# axiom_beta_interface_dummy_v0_13_r1_2_e8.net
KiCad netlist of a schematic drawn in EAGLE
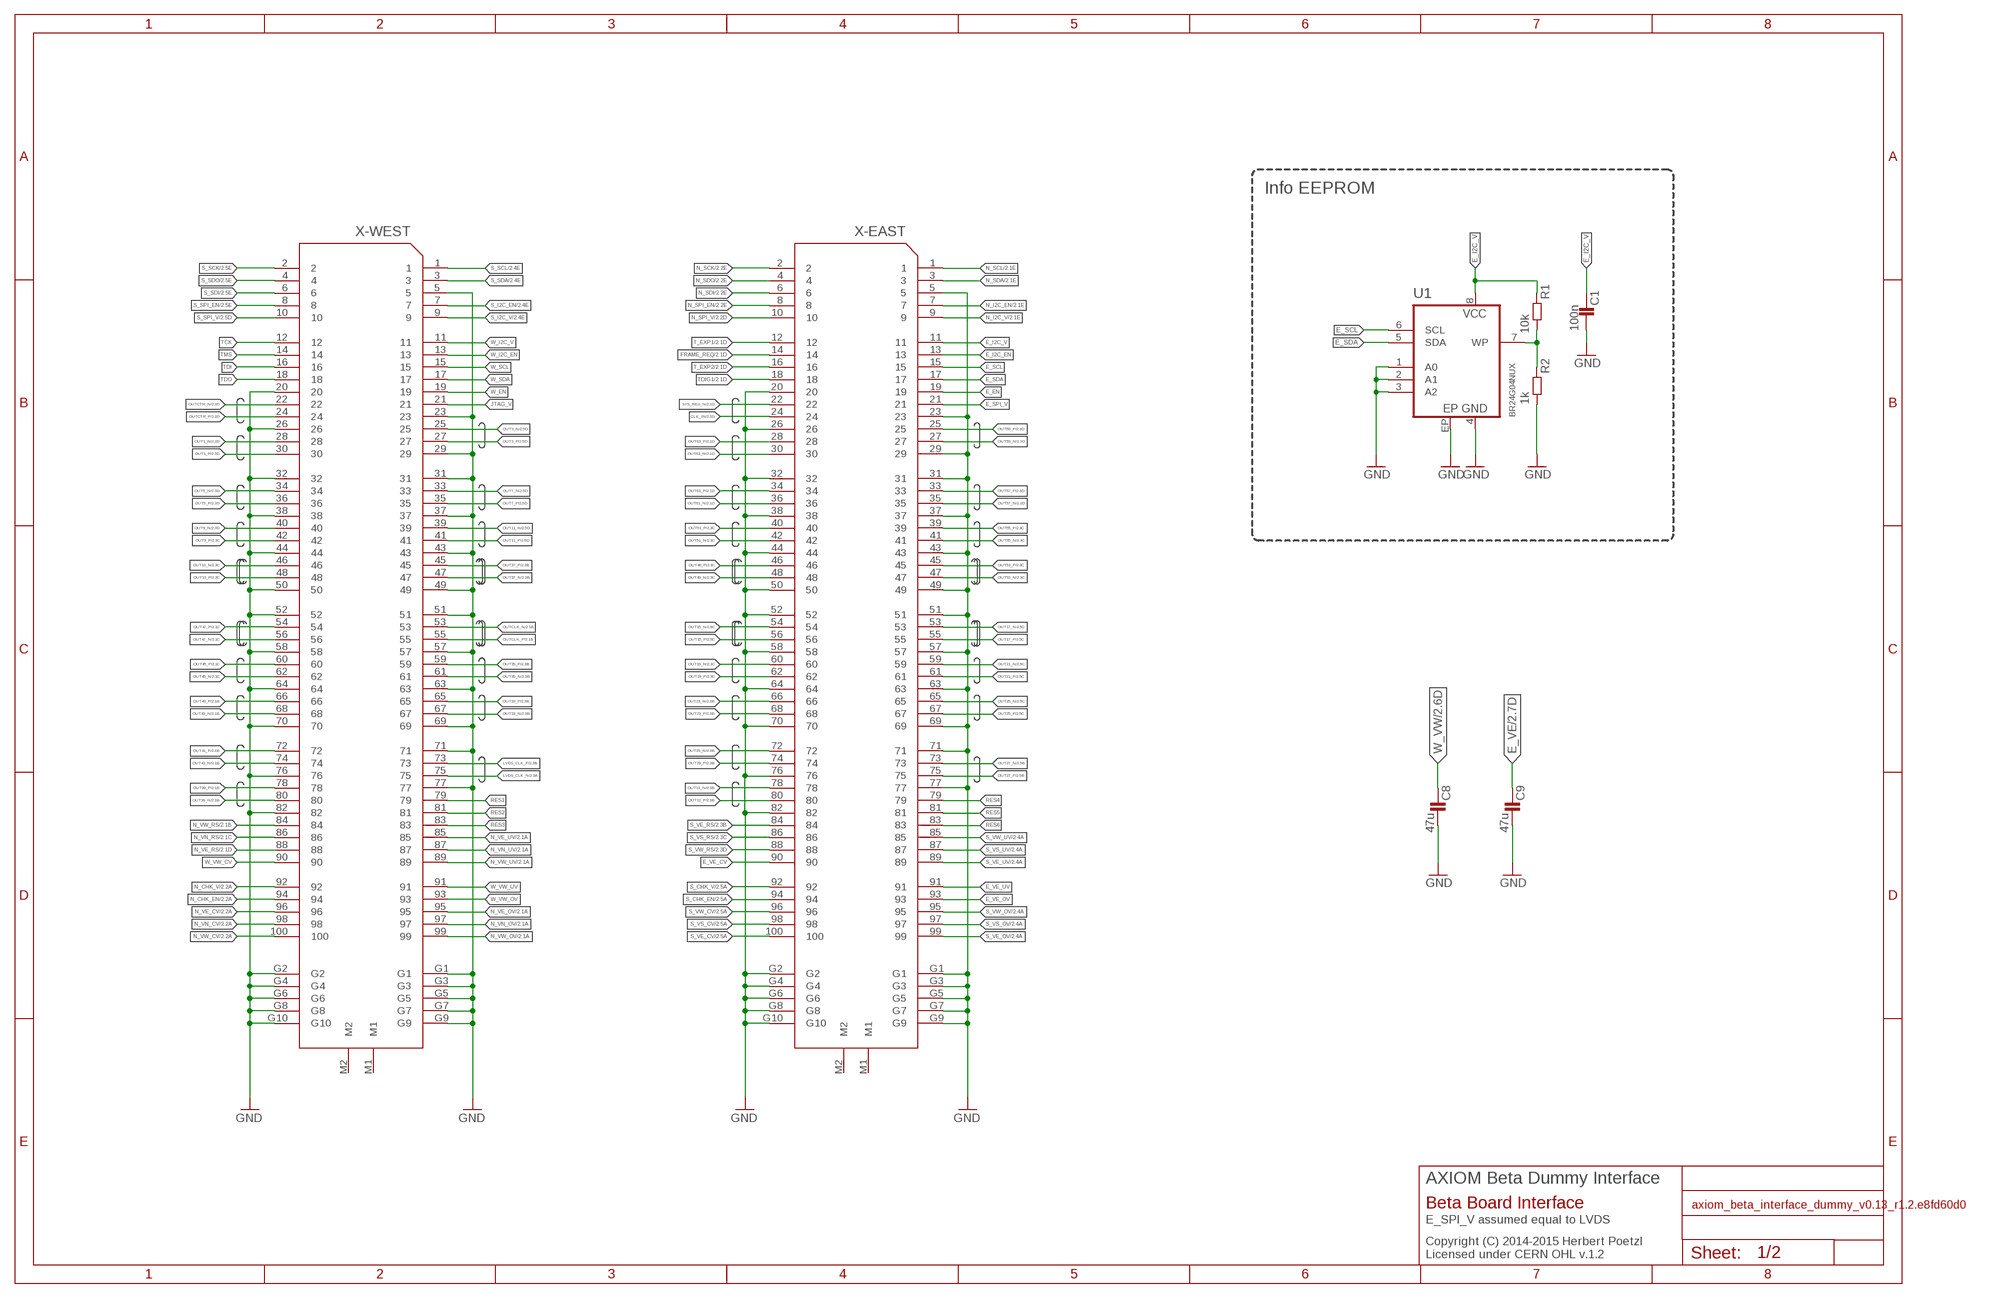
[diagram p0: schematic, sheet 1]
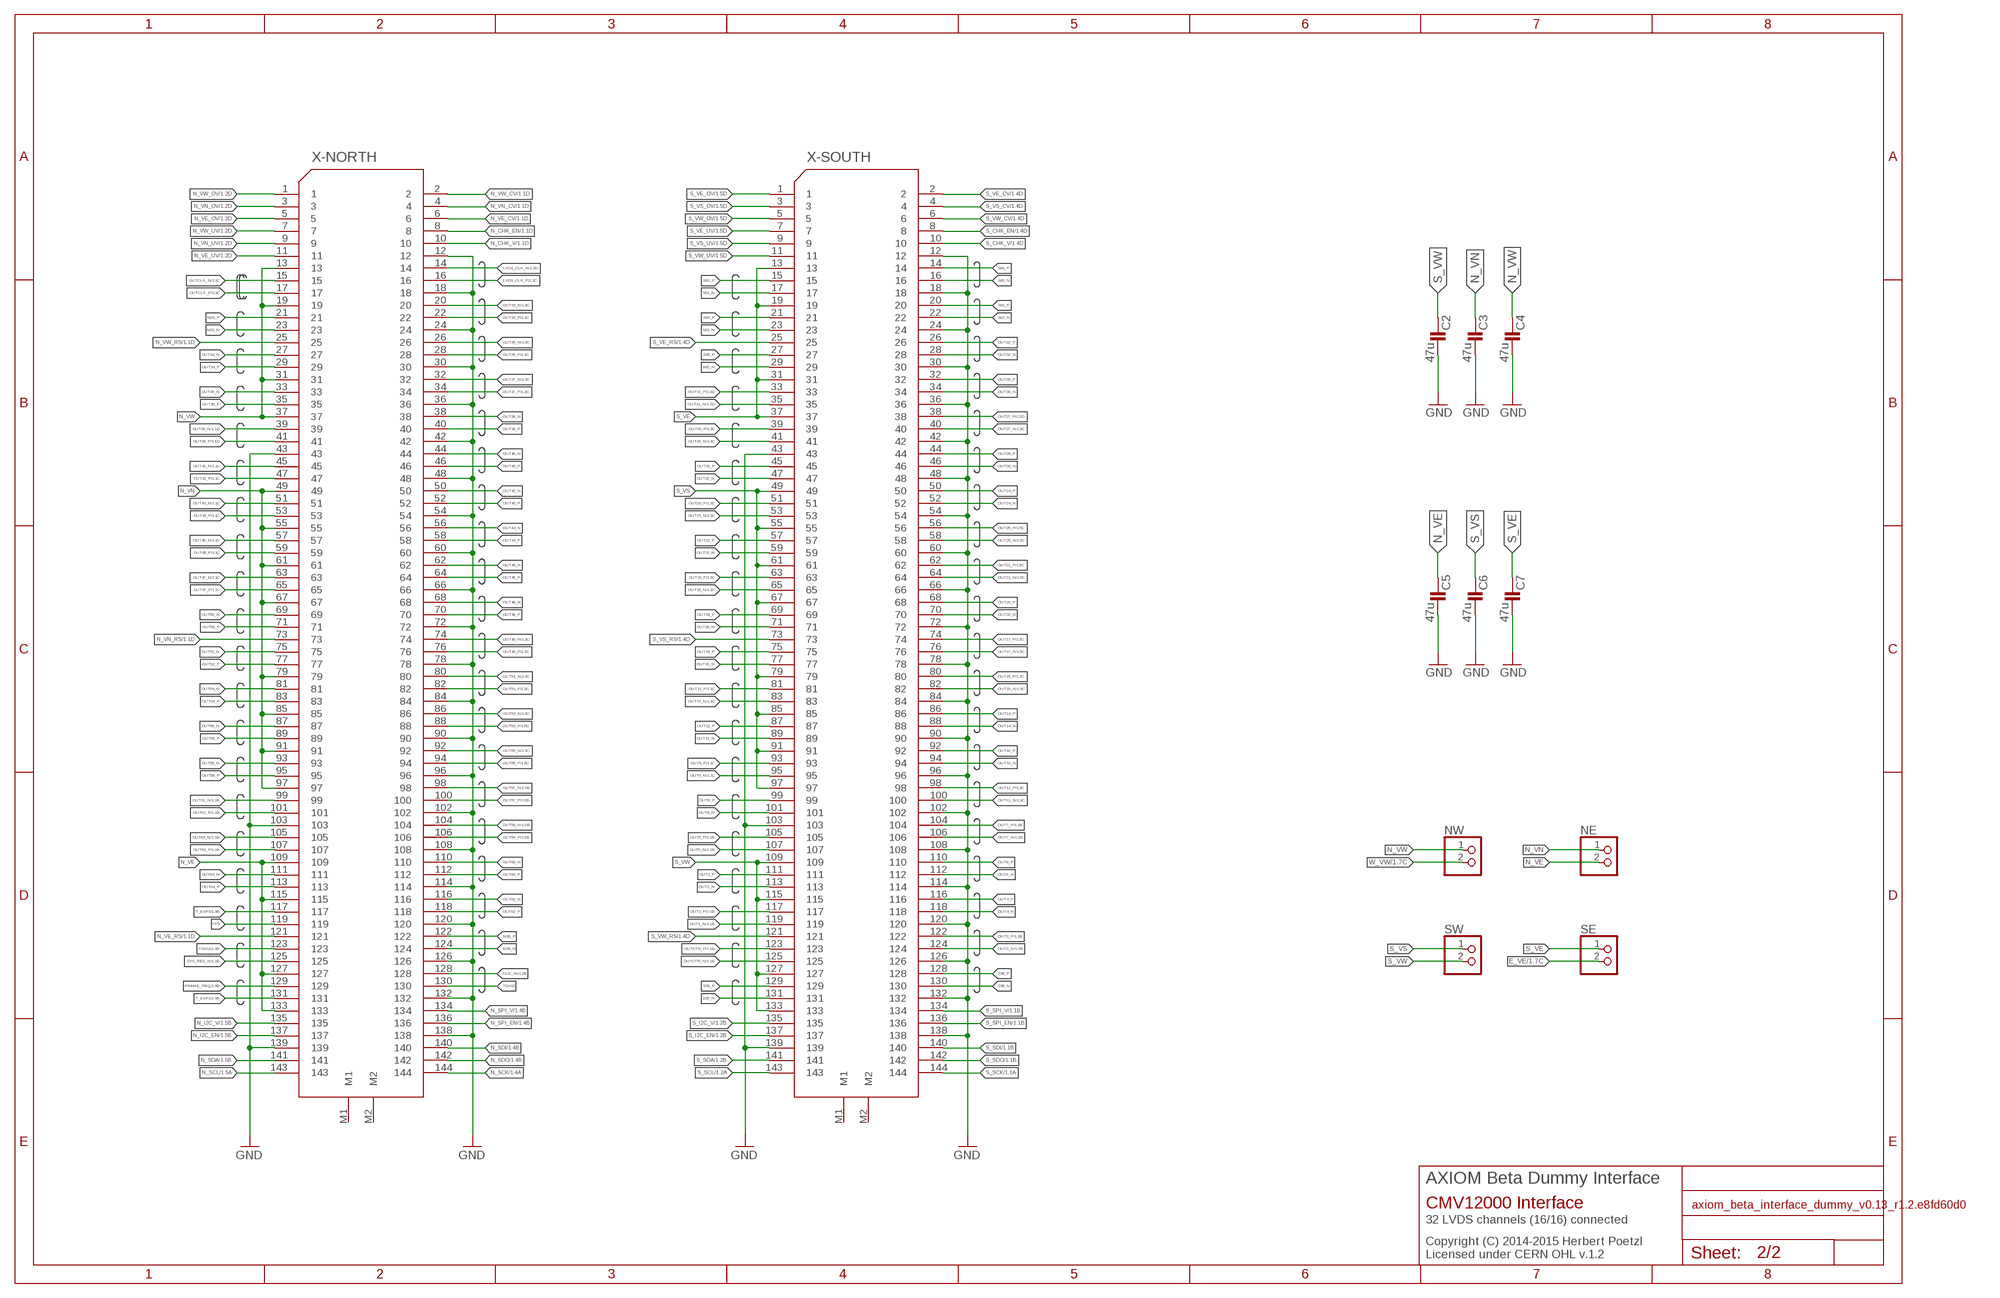
[diagram p1: schematic, sheet 2]

(export (version "E")
  (design (tool "Eeschema 10.0.6"))
  (components
    (comp (ref "C1")
      (value "100n")
      (footprint "eagle-import:0402-B")
      (libsource (lib "eagle-import") (part "C0402-B"))
    )
    (comp (ref "C8")
      (value "47u")
      (footprint "eagle-import:0805-B")
      (libsource (lib "eagle-import") (part "C0805-B"))
    )
    (comp (ref "C9")
      (value "47u")
      (footprint "eagle-import:0805-B")
      (libsource (lib "eagle-import") (part "C0805-B"))
    )
    (comp (ref "R1")
      (value "10k")
      (footprint "eagle-import:0402-B")
      (libsource (lib "eagle-import") (part "R0402-B"))
    )
    (comp (ref "R2")
      (value "1k")
      (footprint "eagle-import:0402-B")
      (libsource (lib "eagle-import") (part "R0402-B"))
    )
    (comp (ref "U1")
      (value "BR24G04NUX")
      (footprint "eagle-import:DFN200X300X100-9N")
      (libsource (lib "eagle-import") (part "BR24G04NUX"))
    )
    (comp (ref "X-EAST")
      (value "FX10-100/10P")
      (footprint "eagle-import:FX10A-100P_10")
      (libsource (lib "eagle-import") (part "FX10-100/10P"))
    )
    (comp (ref "X-WEST")
      (value "FX10-100/10P")
      (footprint "eagle-import:FX10A-100P_10")
      (libsource (lib "eagle-import") (part "FX10-100/10P"))
    )
    (comp (ref "C2")
      (value "47u")
      (footprint "eagle-import:0805-B")
      (libsource (lib "eagle-import") (part "C0805-B"))
    )
    (comp (ref "C3")
      (value "47u")
      (footprint "eagle-import:0805-B")
      (libsource (lib "eagle-import") (part "C0805-B"))
    )
    (comp (ref "C4")
      (value "47u")
      (footprint "eagle-import:0805-B")
      (libsource (lib "eagle-import") (part "C0805-B"))
    )
    (comp (ref "C5")
      (value "47u")
      (footprint "eagle-import:0805-B")
      (libsource (lib "eagle-import") (part "C0805-B"))
    )
    (comp (ref "C6")
      (value "47u")
      (footprint "eagle-import:0805-B")
      (libsource (lib "eagle-import") (part "C0805-B"))
    )
    (comp (ref "C7")
      (value "47u")
      (footprint "eagle-import:0805-B")
      (libsource (lib "eagle-import") (part "C0805-B"))
    )
    (comp (ref "NE")
      (value "PINHD-1X02_2.54")
      (footprint "eagle-import:1X02")
      (libsource (lib "eagle-import") (part "PINHD-1X02_2.54"))
    )
    (comp (ref "NW")
      (value "PINHD-1X02_2.54")
      (footprint "eagle-import:1X02")
      (libsource (lib "eagle-import") (part "PINHD-1X02_2.54"))
    )
    (comp (ref "SE")
      (value "PINHD-1X02_2.54")
      (footprint "eagle-import:1X02")
      (libsource (lib "eagle-import") (part "PINHD-1X02_2.54"))
    )
    (comp (ref "SW")
      (value "PINHD-1X02_2.54")
      (footprint "eagle-import:1X02")
      (libsource (lib "eagle-import") (part "PINHD-1X02_2.54"))
    )
    (comp (ref "X-NORTH")
      (value "FX10-144S")
      (footprint "eagle-import:FX10A-144S")
      (libsource (lib "eagle-import") (part "FX10-144S"))
    )
    (comp (ref "X-SOUTH")
      (value "FX10-144S")
      (footprint "eagle-import:FX10A-144S")
      (libsource (lib "eagle-import") (part "FX10-144S"))
    )
  )
  (nets
    (net (code "1") (name "CLK_IN") (class "Default")
      (node (ref "X-EAST") (pin "24") (pinfunction "24_24") (pintype "bidirectional"))
      (node (ref "X-NORTH") (pin "128") (pinfunction "128_128") (pintype "bidirectional"))
    )
    (net (code "2") (name "E_EN") (class "Default")
      (node (ref "X-EAST") (pin "19") (pinfunction "19_19") (pintype "bidirectional"))
    )
    (net (code "3") (name "E_I2C_EN") (class "Default")
      (node (ref "X-EAST") (pin "13") (pinfunction "13_13") (pintype "bidirectional"))
    )
    (net (code "4") (name "E_I2C_V") (class "Default")
      (node (ref "C1") (pin "1") (pinfunction "1_1") (pintype "passive"))
      (node (ref "R1") (pin "1") (pinfunction "1_1") (pintype "passive"))
      (node (ref "U1") (pin "8") (pinfunction "VCC_8") (pintype "power_in"))
      (node (ref "X-EAST") (pin "11") (pinfunction "11_11") (pintype "bidirectional"))
    )
    (net (code "5") (name "E_SCL") (class "Default")
      (node (ref "U1") (pin "6") (pinfunction "SCL_6") (pintype "input"))
      (node (ref "X-EAST") (pin "15") (pinfunction "15_15") (pintype "bidirectional"))
    )
    (net (code "6") (name "E_SDA") (class "Default")
      (node (ref "U1") (pin "5") (pinfunction "SDA_5") (pintype "bidirectional"))
      (node (ref "X-EAST") (pin "17") (pinfunction "17_17") (pintype "bidirectional"))
    )
    (net (code "7") (name "E_SPI_V") (class "Default")
      (node (ref "X-EAST") (pin "21") (pinfunction "21_21") (pintype "bidirectional"))
    )
    (net (code "8") (name "E_VE") (class "Default")
      (node (ref "C9") (pin "1") (pinfunction "1_1") (pintype "passive"))
      (node (ref "SE") (pin "2") (pinfunction "2_2") (pintype "passive"))
    )
    (net (code "9") (name "E_VE_CV") (class "Default")
      (node (ref "X-EAST") (pin "90") (pinfunction "90_90") (pintype "bidirectional"))
    )
    (net (code "10") (name "E_VE_OV") (class "Default")
      (node (ref "X-EAST") (pin "93") (pinfunction "93_93") (pintype "bidirectional"))
    )
    (net (code "11") (name "E_VE_UV") (class "Default")
      (node (ref "X-EAST") (pin "91") (pinfunction "91_91") (pintype "bidirectional"))
    )
    (net (code "12") (name "FRAME_REQ") (class "Default")
      (node (ref "X-EAST") (pin "14") (pinfunction "14_14") (pintype "bidirectional"))
      (node (ref "X-NORTH") (pin "129") (pinfunction "129_129") (pintype "bidirectional"))
    )
    (net (code "13") (name "GND") (class "Default")
      (node (ref "C1") (pin "2") (pinfunction "2_2") (pintype "passive"))
      (node (ref "C2") (pin "2") (pinfunction "2_2") (pintype "passive"))
      (node (ref "C3") (pin "2") (pinfunction "2_2") (pintype "passive"))
      (node (ref "C4") (pin "2") (pinfunction "2_2") (pintype "passive"))
      (node (ref "C5") (pin "2") (pinfunction "2_2") (pintype "passive"))
      (node (ref "C6") (pin "2") (pinfunction "2_2") (pintype "passive"))
      (node (ref "C7") (pin "2") (pinfunction "2_2") (pintype "passive"))
      (node (ref "C8") (pin "2") (pinfunction "2_2") (pintype "passive"))
      (node (ref "C9") (pin "2") (pinfunction "2_2") (pintype "passive"))
      (node (ref "R2") (pin "2") (pinfunction "2_2") (pintype "passive"))
      (node (ref "U1") (pin "1") (pinfunction "A0_1") (pintype "input"))
      (node (ref "U1") (pin "2") (pinfunction "A1_2") (pintype "input"))
      (node (ref "U1") (pin "3") (pinfunction "A2_3") (pintype "input"))
      (node (ref "U1") (pin "4") (pinfunction "GND_4") (pintype "passive"))
      (node (ref "U1") (pin "EP") (pinfunction "EP_EP") (pintype "passive"))
      (node (ref "X-EAST") (pin "20") (pinfunction "20_20") (pintype "bidirectional"))
      (node (ref "X-EAST") (pin "23") (pinfunction "23_23") (pintype "bidirectional"))
      (node (ref "X-EAST") (pin "26") (pinfunction "26_26") (pintype "bidirectional"))
      (node (ref "X-EAST") (pin "29") (pinfunction "29_29") (pintype "bidirectional"))
      (node (ref "X-EAST") (pin "31") (pinfunction "31_31") (pintype "bidirectional"))
      (node (ref "X-EAST") (pin "32") (pinfunction "32_32") (pintype "bidirectional"))
      (node (ref "X-EAST") (pin "37") (pinfunction "37_37") (pintype "bidirectional"))
      (node (ref "X-EAST") (pin "38") (pinfunction "38_38") (pintype "bidirectional"))
      (node (ref "X-EAST") (pin "43") (pinfunction "43_43") (pintype "bidirectional"))
      (node (ref "X-EAST") (pin "44") (pinfunction "44_44") (pintype "bidirectional"))
      (node (ref "X-EAST") (pin "49") (pinfunction "49_49") (pintype "bidirectional"))
      (node (ref "X-EAST") (pin "5") (pinfunction "5_5") (pintype "bidirectional"))
      (node (ref "X-EAST") (pin "50") (pinfunction "50_50") (pintype "bidirectional"))
      (node (ref "X-EAST") (pin "51") (pinfunction "51_51") (pintype "bidirectional"))
      (node (ref "X-EAST") (pin "52") (pinfunction "52_52") (pintype "bidirectional"))
      (node (ref "X-EAST") (pin "57") (pinfunction "57_57") (pintype "bidirectional"))
      (node (ref "X-EAST") (pin "58") (pinfunction "58_58") (pintype "bidirectional"))
      (node (ref "X-EAST") (pin "63") (pinfunction "63_63") (pintype "bidirectional"))
      (node (ref "X-EAST") (pin "64") (pinfunction "64_64") (pintype "bidirectional"))
      (node (ref "X-EAST") (pin "69") (pinfunction "69_69") (pintype "bidirectional"))
      (node (ref "X-EAST") (pin "70") (pinfunction "70_70") (pintype "bidirectional"))
      (node (ref "X-EAST") (pin "71") (pinfunction "71_71") (pintype "bidirectional"))
      (node (ref "X-EAST") (pin "76") (pinfunction "76_76") (pintype "bidirectional"))
      (node (ref "X-EAST") (pin "77") (pinfunction "77_77") (pintype "bidirectional"))
      (node (ref "X-EAST") (pin "82") (pinfunction "82_82") (pintype "bidirectional"))
      (node (ref "X-EAST") (pin "G1") (pinfunction "G1_G1") (pintype "bidirectional"))
      (node (ref "X-EAST") (pin "G10") (pinfunction "G10_G10") (pintype "bidirectional"))
      (node (ref "X-EAST") (pin "G2") (pinfunction "G2_G2") (pintype "bidirectional"))
      (node (ref "X-EAST") (pin "G3") (pinfunction "G3_G3") (pintype "bidirectional"))
      (node (ref "X-EAST") (pin "G4") (pinfunction "G4_G4") (pintype "bidirectional"))
      (node (ref "X-EAST") (pin "G5") (pinfunction "G5_G5") (pintype "bidirectional"))
      (node (ref "X-EAST") (pin "G6") (pinfunction "G6_G6") (pintype "bidirectional"))
      (node (ref "X-EAST") (pin "G7") (pinfunction "G7_G7") (pintype "bidirectional"))
      (node (ref "X-EAST") (pin "G8") (pinfunction "G8_G8") (pintype "bidirectional"))
      (node (ref "X-EAST") (pin "G9") (pinfunction "G9_G9") (pintype "bidirectional"))
      (node (ref "X-NORTH") (pin "102") (pinfunction "102_102") (pintype "bidirectional"))
      (node (ref "X-NORTH") (pin "103") (pinfunction "103_103") (pintype "bidirectional"))
      (node (ref "X-NORTH") (pin "108") (pinfunction "108_108") (pintype "bidirectional"))
      (node (ref "X-NORTH") (pin "114") (pinfunction "114_114") (pintype "bidirectional"))
      (node (ref "X-NORTH") (pin "12") (pinfunction "12_12") (pintype "bidirectional"))
      (node (ref "X-NORTH") (pin "120") (pinfunction "120_120") (pintype "bidirectional"))
      (node (ref "X-NORTH") (pin "126") (pinfunction "126_126") (pintype "bidirectional"))
      (node (ref "X-NORTH") (pin "132") (pinfunction "132_132") (pintype "bidirectional"))
      (node (ref "X-NORTH") (pin "138") (pinfunction "138_138") (pintype "bidirectional"))
      (node (ref "X-NORTH") (pin "139") (pinfunction "139_139") (pintype "bidirectional"))
      (node (ref "X-NORTH") (pin "18") (pinfunction "18_18") (pintype "bidirectional"))
      (node (ref "X-NORTH") (pin "24") (pinfunction "24_24") (pintype "bidirectional"))
      (node (ref "X-NORTH") (pin "30") (pinfunction "30_30") (pintype "bidirectional"))
      (node (ref "X-NORTH") (pin "36") (pinfunction "36_36") (pintype "bidirectional"))
      (node (ref "X-NORTH") (pin "42") (pinfunction "42_42") (pintype "bidirectional"))
      (node (ref "X-NORTH") (pin "43") (pinfunction "43_43") (pintype "bidirectional"))
      (node (ref "X-NORTH") (pin "48") (pinfunction "48_48") (pintype "bidirectional"))
      (node (ref "X-NORTH") (pin "54") (pinfunction "54_54") (pintype "bidirectional"))
      (node (ref "X-NORTH") (pin "60") (pinfunction "60_60") (pintype "bidirectional"))
      (node (ref "X-NORTH") (pin "66") (pinfunction "66_66") (pintype "bidirectional"))
      (node (ref "X-NORTH") (pin "72") (pinfunction "72_72") (pintype "bidirectional"))
      (node (ref "X-NORTH") (pin "78") (pinfunction "78_78") (pintype "bidirectional"))
      (node (ref "X-NORTH") (pin "84") (pinfunction "84_84") (pintype "bidirectional"))
      (node (ref "X-NORTH") (pin "90") (pinfunction "90_90") (pintype "bidirectional"))
      (node (ref "X-NORTH") (pin "96") (pinfunction "96_96") (pintype "bidirectional"))
      (node (ref "X-SOUTH") (pin "102") (pinfunction "102_102") (pintype "bidirectional"))
      (node (ref "X-SOUTH") (pin "103") (pinfunction "103_103") (pintype "bidirectional"))
      (node (ref "X-SOUTH") (pin "108") (pinfunction "108_108") (pintype "bidirectional"))
      (node (ref "X-SOUTH") (pin "114") (pinfunction "114_114") (pintype "bidirectional"))
      (node (ref "X-SOUTH") (pin "12") (pinfunction "12_12") (pintype "bidirectional"))
      (node (ref "X-SOUTH") (pin "120") (pinfunction "120_120") (pintype "bidirectional"))
      (node (ref "X-SOUTH") (pin "126") (pinfunction "126_126") (pintype "bidirectional"))
      (node (ref "X-SOUTH") (pin "132") (pinfunction "132_132") (pintype "bidirectional"))
      (node (ref "X-SOUTH") (pin "138") (pinfunction "138_138") (pintype "bidirectional"))
      (node (ref "X-SOUTH") (pin "139") (pinfunction "139_139") (pintype "bidirectional"))
      (node (ref "X-SOUTH") (pin "18") (pinfunction "18_18") (pintype "bidirectional"))
      (node (ref "X-SOUTH") (pin "24") (pinfunction "24_24") (pintype "bidirectional"))
      (node (ref "X-SOUTH") (pin "30") (pinfunction "30_30") (pintype "bidirectional"))
      (node (ref "X-SOUTH") (pin "36") (pinfunction "36_36") (pintype "bidirectional"))
      (node (ref "X-SOUTH") (pin "42") (pinfunction "42_42") (pintype "bidirectional"))
      (node (ref "X-SOUTH") (pin "43") (pinfunction "43_43") (pintype "bidirectional"))
      (node (ref "X-SOUTH") (pin "48") (pinfunction "48_48") (pintype "bidirectional"))
      (node (ref "X-SOUTH") (pin "54") (pinfunction "54_54") (pintype "bidirectional"))
      (node (ref "X-SOUTH") (pin "60") (pinfunction "60_60") (pintype "bidirectional"))
      (node (ref "X-SOUTH") (pin "66") (pinfunction "66_66") (pintype "bidirectional"))
      (node (ref "X-SOUTH") (pin "72") (pinfunction "72_72") (pintype "bidirectional"))
      (node (ref "X-SOUTH") (pin "78") (pinfunction "78_78") (pintype "bidirectional"))
      (node (ref "X-SOUTH") (pin "84") (pinfunction "84_84") (pintype "bidirectional"))
      (node (ref "X-SOUTH") (pin "90") (pinfunction "90_90") (pintype "bidirectional"))
      (node (ref "X-SOUTH") (pin "96") (pinfunction "96_96") (pintype "bidirectional"))
      (node (ref "X-WEST") (pin "20") (pinfunction "20_20") (pintype "bidirectional"))
      (node (ref "X-WEST") (pin "23") (pinfunction "23_23") (pintype "bidirectional"))
      (node (ref "X-WEST") (pin "26") (pinfunction "26_26") (pintype "bidirectional"))
      (node (ref "X-WEST") (pin "29") (pinfunction "29_29") (pintype "bidirectional"))
      (node (ref "X-WEST") (pin "31") (pinfunction "31_31") (pintype "bidirectional"))
      (node (ref "X-WEST") (pin "32") (pinfunction "32_32") (pintype "bidirectional"))
      (node (ref "X-WEST") (pin "37") (pinfunction "37_37") (pintype "bidirectional"))
      (node (ref "X-WEST") (pin "38") (pinfunction "38_38") (pintype "bidirectional"))
      (node (ref "X-WEST") (pin "43") (pinfunction "43_43") (pintype "bidirectional"))
      (node (ref "X-WEST") (pin "44") (pinfunction "44_44") (pintype "bidirectional"))
      (node (ref "X-WEST") (pin "49") (pinfunction "49_49") (pintype "bidirectional"))
      (node (ref "X-WEST") (pin "5") (pinfunction "5_5") (pintype "bidirectional"))
      (node (ref "X-WEST") (pin "50") (pinfunction "50_50") (pintype "bidirectional"))
      (node (ref "X-WEST") (pin "51") (pinfunction "51_51") (pintype "bidirectional"))
      (node (ref "X-WEST") (pin "52") (pinfunction "52_52") (pintype "bidirectional"))
      (node (ref "X-WEST") (pin "57") (pinfunction "57_57") (pintype "bidirectional"))
      (node (ref "X-WEST") (pin "58") (pinfunction "58_58") (pintype "bidirectional"))
      (node (ref "X-WEST") (pin "63") (pinfunction "63_63") (pintype "bidirectional"))
      (node (ref "X-WEST") (pin "64") (pinfunction "64_64") (pintype "bidirectional"))
      (node (ref "X-WEST") (pin "69") (pinfunction "69_69") (pintype "bidirectional"))
      (node (ref "X-WEST") (pin "70") (pinfunction "70_70") (pintype "bidirectional"))
      (node (ref "X-WEST") (pin "71") (pinfunction "71_71") (pintype "bidirectional"))
      (node (ref "X-WEST") (pin "76") (pinfunction "76_76") (pintype "bidirectional"))
      (node (ref "X-WEST") (pin "77") (pinfunction "77_77") (pintype "bidirectional"))
      (node (ref "X-WEST") (pin "82") (pinfunction "82_82") (pintype "bidirectional"))
      (node (ref "X-WEST") (pin "G1") (pinfunction "G1_G1") (pintype "bidirectional"))
      (node (ref "X-WEST") (pin "G10") (pinfunction "G10_G10") (pintype "bidirectional"))
      (node (ref "X-WEST") (pin "G2") (pinfunction "G2_G2") (pintype "bidirectional"))
      (node (ref "X-WEST") (pin "G3") (pinfunction "G3_G3") (pintype "bidirectional"))
      (node (ref "X-WEST") (pin "G4") (pinfunction "G4_G4") (pintype "bidirectional"))
      (node (ref "X-WEST") (pin "G5") (pinfunction "G5_G5") (pintype "bidirectional"))
      (node (ref "X-WEST") (pin "G6") (pinfunction "G6_G6") (pintype "bidirectional"))
      (node (ref "X-WEST") (pin "G7") (pinfunction "G7_G7") (pintype "bidirectional"))
      (node (ref "X-WEST") (pin "G8") (pinfunction "G8_G8") (pintype "bidirectional"))
      (node (ref "X-WEST") (pin "G9") (pinfunction "G9_G9") (pintype "bidirectional"))
    )
    (net (code "14") (name "JTAG_V") (class "Default")
      (node (ref "X-WEST") (pin "21") (pinfunction "21_21") (pintype "bidirectional"))
    )
    (net (code "15") (name "LVDS_CLK_N") (class "Default")
      (node (ref "X-NORTH") (pin "14") (pinfunction "14_14") (pintype "bidirectional"))
      (node (ref "X-WEST") (pin "75") (pinfunction "75_75") (pintype "bidirectional"))
    )
    (net (code "16") (name "LVDS_CLK_P") (class "Default")
      (node (ref "X-NORTH") (pin "16") (pinfunction "16_16") (pintype "bidirectional"))
      (node (ref "X-WEST") (pin "73") (pinfunction "73_73") (pintype "bidirectional"))
    )
    (net (code "17") (name "N03_N") (class "Default")
      (node (ref "X-NORTH") (pin "23") (pinfunction "23_23") (pintype "bidirectional"))
    )
    (net (code "18") (name "N03_P") (class "Default")
      (node (ref "X-NORTH") (pin "21") (pinfunction "21_21") (pintype "bidirectional"))
    )
    (net (code "19") (name "N36_N") (class "Default")
      (node (ref "X-NORTH") (pin "124") (pinfunction "124_124") (pintype "bidirectional"))
    )
    (net (code "20") (name "N36_P") (class "Default")
      (node (ref "X-NORTH") (pin "122") (pinfunction "122_122") (pintype "bidirectional"))
    )
    (net (code "21") (name "N_CHK_EN") (class "Default")
      (node (ref "X-NORTH") (pin "8") (pinfunction "8_8") (pintype "bidirectional"))
      (node (ref "X-WEST") (pin "94") (pinfunction "94_94") (pintype "bidirectional"))
    )
    (net (code "22") (name "N_CHK_V") (class "Default")
      (node (ref "X-NORTH") (pin "10") (pinfunction "10_10") (pintype "bidirectional"))
      (node (ref "X-WEST") (pin "92") (pinfunction "92_92") (pintype "bidirectional"))
    )
    (net (code "23") (name "N_I2C_EN") (class "Default")
      (node (ref "X-EAST") (pin "7") (pinfunction "7_7") (pintype "bidirectional"))
      (node (ref "X-NORTH") (pin "137") (pinfunction "137_137") (pintype "bidirectional"))
    )
    (net (code "24") (name "N_I2C_V") (class "Default")
      (node (ref "X-EAST") (pin "9") (pinfunction "9_9") (pintype "bidirectional"))
      (node (ref "X-NORTH") (pin "135") (pinfunction "135_135") (pintype "bidirectional"))
    )
    (net (code "25") (name "N_SCK") (class "Default")
      (node (ref "X-EAST") (pin "2") (pinfunction "2_2") (pintype "bidirectional"))
      (node (ref "X-NORTH") (pin "144") (pinfunction "144_144") (pintype "bidirectional"))
    )
    (net (code "26") (name "N_SCL") (class "Default")
      (node (ref "X-EAST") (pin "1") (pinfunction "1_1") (pintype "bidirectional"))
      (node (ref "X-NORTH") (pin "143") (pinfunction "143_143") (pintype "bidirectional"))
    )
    (net (code "27") (name "N_SDA") (class "Default")
      (node (ref "X-EAST") (pin "3") (pinfunction "3_3") (pintype "bidirectional"))
      (node (ref "X-NORTH") (pin "141") (pinfunction "141_141") (pintype "bidirectional"))
    )
    (net (code "28") (name "N_SDI") (class "Default")
      (node (ref "X-EAST") (pin "6") (pinfunction "6_6") (pintype "bidirectional"))
      (node (ref "X-NORTH") (pin "140") (pinfunction "140_140") (pintype "bidirectional"))
    )
    (net (code "29") (name "N_SDO") (class "Default")
      (node (ref "X-EAST") (pin "4") (pinfunction "4_4") (pintype "bidirectional"))
      (node (ref "X-NORTH") (pin "142") (pinfunction "142_142") (pintype "bidirectional"))
    )
    (net (code "30") (name "N_SPI_EN") (class "Default")
      (node (ref "X-EAST") (pin "8") (pinfunction "8_8") (pintype "bidirectional"))
      (node (ref "X-NORTH") (pin "136") (pinfunction "136_136") (pintype "bidirectional"))
    )
    (net (code "31") (name "N_SPI_V") (class "Default")
      (node (ref "X-EAST") (pin "10") (pinfunction "10_10") (pintype "bidirectional"))
      (node (ref "X-NORTH") (pin "134") (pinfunction "134_134") (pintype "bidirectional"))
    )
    (net (code "32") (name "N_VE") (class "Default")
      (node (ref "C5") (pin "1") (pinfunction "1_1") (pintype "passive"))
      (node (ref "NE") (pin "2") (pinfunction "2_2") (pintype "passive"))
      (node (ref "X-NORTH") (pin "109") (pinfunction "109_109") (pintype "bidirectional"))
      (node (ref "X-NORTH") (pin "115") (pinfunction "115_115") (pintype "bidirectional"))
      (node (ref "X-NORTH") (pin "127") (pinfunction "127_127") (pintype "bidirectional"))
      (node (ref "X-NORTH") (pin "133") (pinfunction "133_133") (pintype "bidirectional"))
    )
    (net (code "33") (name "N_VE_CV") (class "Default")
      (node (ref "X-NORTH") (pin "6") (pinfunction "6_6") (pintype "bidirectional"))
      (node (ref "X-WEST") (pin "96") (pinfunction "96_96") (pintype "bidirectional"))
    )
    (net (code "34") (name "N_VE_OV") (class "Default")
      (node (ref "X-NORTH") (pin "5") (pinfunction "5_5") (pintype "bidirectional"))
      (node (ref "X-WEST") (pin "95") (pinfunction "95_95") (pintype "bidirectional"))
    )
    (net (code "35") (name "N_VE_RS") (class "Default")
      (node (ref "X-NORTH") (pin "121") (pinfunction "121_121") (pintype "bidirectional"))
      (node (ref "X-WEST") (pin "88") (pinfunction "88_88") (pintype "bidirectional"))
    )
    (net (code "36") (name "N_VE_UV") (class "Default")
      (node (ref "X-NORTH") (pin "11") (pinfunction "11_11") (pintype "bidirectional"))
      (node (ref "X-WEST") (pin "85") (pinfunction "85_85") (pintype "bidirectional"))
    )
    (net (code "37") (name "N_VN") (class "Default")
      (node (ref "C3") (pin "1") (pinfunction "1_1") (pintype "passive"))
      (node (ref "NE") (pin "1") (pinfunction "1_1") (pintype "passive"))
      (node (ref "X-NORTH") (pin "49") (pinfunction "49_49") (pintype "bidirectional"))
      (node (ref "X-NORTH") (pin "55") (pinfunction "55_55") (pintype "bidirectional"))
      (node (ref "X-NORTH") (pin "61") (pinfunction "61_61") (pintype "bidirectional"))
      (node (ref "X-NORTH") (pin "67") (pinfunction "67_67") (pintype "bidirectional"))
      (node (ref "X-NORTH") (pin "79") (pinfunction "79_79") (pintype "bidirectional"))
      (node (ref "X-NORTH") (pin "85") (pinfunction "85_85") (pintype "bidirectional"))
      (node (ref "X-NORTH") (pin "91") (pinfunction "91_91") (pintype "bidirectional"))
      (node (ref "X-NORTH") (pin "97") (pinfunction "97_97") (pintype "bidirectional"))
    )
    (net (code "38") (name "N_VN_CV") (class "Default")
      (node (ref "X-NORTH") (pin "4") (pinfunction "4_4") (pintype "bidirectional"))
      (node (ref "X-WEST") (pin "98") (pinfunction "98_98") (pintype "bidirectional"))
    )
    (net (code "39") (name "N_VN_OV") (class "Default")
      (node (ref "X-NORTH") (pin "3") (pinfunction "3_3") (pintype "bidirectional"))
      (node (ref "X-WEST") (pin "97") (pinfunction "97_97") (pintype "bidirectional"))
    )
    (net (code "40") (name "N_VN_RS") (class "Default")
      (node (ref "X-NORTH") (pin "73") (pinfunction "73_73") (pintype "bidirectional"))
      (node (ref "X-WEST") (pin "86") (pinfunction "86_86") (pintype "bidirectional"))
    )
    (net (code "41") (name "N_VN_UV") (class "Default")
      (node (ref "X-NORTH") (pin "9") (pinfunction "9_9") (pintype "bidirectional"))
      (node (ref "X-WEST") (pin "87") (pinfunction "87_87") (pintype "bidirectional"))
    )
    (net (code "42") (name "N_VW") (class "Default")
      (node (ref "C4") (pin "1") (pinfunction "1_1") (pintype "passive"))
      (node (ref "NW") (pin "1") (pinfunction "1_1") (pintype "passive"))
      (node (ref "X-NORTH") (pin "13") (pinfunction "13_13") (pintype "bidirectional"))
      (node (ref "X-NORTH") (pin "19") (pinfunction "19_19") (pintype "bidirectional"))
      (node (ref "X-NORTH") (pin "31") (pinfunction "31_31") (pintype "bidirectional"))
      (node (ref "X-NORTH") (pin "37") (pinfunction "37_37") (pintype "bidirectional"))
    )
    (net (code "43") (name "N_VW_CV") (class "Default")
      (node (ref "X-NORTH") (pin "2") (pinfunction "2_2") (pintype "bidirectional"))
      (node (ref "X-WEST") (pin "100") (pinfunction "100_100") (pintype "bidirectional"))
    )
    (net (code "44") (name "N_VW_OV") (class "Default")
      (node (ref "X-NORTH") (pin "1") (pinfunction "1_1") (pintype "bidirectional"))
      (node (ref "X-WEST") (pin "99") (pinfunction "99_99") (pintype "bidirectional"))
    )
    (net (code "45") (name "N_VW_RS") (class "Default")
      (node (ref "X-NORTH") (pin "25") (pinfunction "25_25") (pintype "bidirectional"))
      (node (ref "X-WEST") (pin "84") (pinfunction "84_84") (pintype "bidirectional"))
    )
    (net (code "46") (name "N_VW_UV") (class "Default")
      (node (ref "X-NORTH") (pin "7") (pinfunction "7_7") (pintype "bidirectional"))
      (node (ref "X-WEST") (pin "89") (pinfunction "89_89") (pintype "bidirectional"))
    )
    (net (code "47") (name "Net-(U1-WP)") (class "Default")
      (node (ref "R1") (pin "2") (pinfunction "2_2") (pintype "passive"))
      (node (ref "R2") (pin "1") (pinfunction "1_1") (pintype "passive"))
      (node (ref "U1") (pin "7") (pinfunction "WP_7") (pintype "input"))
    )
    (net (code "48") (name "OUT1_N") (class "Default")
      (node (ref "X-SOUTH") (pin "119") (pinfunction "119_119") (pintype "bidirectional"))
      (node (ref "X-WEST") (pin "28") (pinfunction "28_28") (pintype "bidirectional"))
    )
    (net (code "49") (name "OUT1_P") (class "Default")
      (node (ref "X-SOUTH") (pin "117") (pinfunction "117_117") (pintype "bidirectional"))
      (node (ref "X-WEST") (pin "30") (pinfunction "30_30") (pintype "bidirectional"))
    )
    (net (code "50") (name "OUT2_N") (class "Default")
      (node (ref "X-SOUTH") (pin "113") (pinfunction "113_113") (pintype "bidirectional"))
    )
    (net (code "51") (name "OUT2_P") (class "Default")
      (node (ref "X-SOUTH") (pin "111") (pinfunction "111_111") (pintype "bidirectional"))
    )
    (net (code "52") (name "OUT3_N") (class "Default")
      (node (ref "X-SOUTH") (pin "124") (pinfunction "124_124") (pintype "bidirectional"))
      (node (ref "X-WEST") (pin "25") (pinfunction "25_25") (pintype "bidirectional"))
    )
    (net (code "53") (name "OUT3_P") (class "Default")
      (node (ref "X-SOUTH") (pin "122") (pinfunction "122_122") (pintype "bidirectional"))
      (node (ref "X-WEST") (pin "27") (pinfunction "27_27") (pintype "bidirectional"))
    )
    (net (code "54") (name "OUT4_N") (class "Default")
      (node (ref "X-SOUTH") (pin "118") (pinfunction "118_118") (pintype "bidirectional"))
    )
    (net (code "55") (name "OUT4_P") (class "Default")
      (node (ref "X-SOUTH") (pin "116") (pinfunction "116_116") (pintype "bidirectional"))
    )
    (net (code "56") (name "OUT5_N") (class "Default")
      (node (ref "X-SOUTH") (pin "107") (pinfunction "107_107") (pintype "bidirectional"))
      (node (ref "X-WEST") (pin "34") (pinfunction "34_34") (pintype "bidirectional"))
    )
    (net (code "57") (name "OUT5_P") (class "Default")
      (node (ref "X-SOUTH") (pin "105") (pinfunction "105_105") (pintype "bidirectional"))
      (node (ref "X-WEST") (pin "36") (pinfunction "36_36") (pintype "bidirectional"))
    )
    (net (code "58") (name "OUT6_N") (class "Default")
      (node (ref "X-SOUTH") (pin "112") (pinfunction "112_112") (pintype "bidirectional"))
    )
    (net (code "59") (name "OUT6_P") (class "Default")
      (node (ref "X-SOUTH") (pin "110") (pinfunction "110_110") (pintype "bidirectional"))
    )
    (net (code "60") (name "OUT7_N") (class "Default")
      (node (ref "X-SOUTH") (pin "106") (pinfunction "106_106") (pintype "bidirectional"))
      (node (ref "X-WEST") (pin "33") (pinfunction "33_33") (pintype "bidirectional"))
    )
    (net (code "61") (name "OUT7_P") (class "Default")
      (node (ref "X-SOUTH") (pin "104") (pinfunction "104_104") (pintype "bidirectional"))
      (node (ref "X-WEST") (pin "35") (pinfunction "35_35") (pintype "bidirectional"))
    )
    (net (code "62") (name "OUT8_N") (class "Default")
      (node (ref "X-SOUTH") (pin "101") (pinfunction "101_101") (pintype "bidirectional"))
    )
    (net (code "63") (name "OUT8_P") (class "Default")
      (node (ref "X-SOUTH") (pin "99") (pinfunction "99_99") (pintype "bidirectional"))
    )
    (net (code "64") (name "OUT9_N") (class "Default")
      (node (ref "X-SOUTH") (pin "95") (pinfunction "95_95") (pintype "bidirectional"))
      (node (ref "X-WEST") (pin "40") (pinfunction "40_40") (pintype "bidirectional"))
    )
    (net (code "65") (name "OUT9_P") (class "Default")
      (node (ref "X-SOUTH") (pin "93") (pinfunction "93_93") (pintype "bidirectional"))
      (node (ref "X-WEST") (pin "42") (pinfunction "42_42") (pintype "bidirectional"))
    )
    (net (code "66") (name "OUT10_N") (class "Default")
      (node (ref "X-SOUTH") (pin "94") (pinfunction "94_94") (pintype "bidirectional"))
    )
    (net (code "67") (name "OUT10_P") (class "Default")
      (node (ref "X-SOUTH") (pin "92") (pinfunction "92_92") (pintype "bidirectional"))
    )
    (net (code "68") (name "OUT11_N") (class "Default")
      (node (ref "X-SOUTH") (pin "100") (pinfunction "100_100") (pintype "bidirectional"))
      (node (ref "X-WEST") (pin "39") (pinfunction "39_39") (pintype "bidirectional"))
    )
    (net (code "69") (name "OUT11_P") (class "Default")
      (node (ref "X-SOUTH") (pin "98") (pinfunction "98_98") (pintype "bidirectional"))
      (node (ref "X-WEST") (pin "41") (pinfunction "41_41") (pintype "bidirectional"))
    )
    (net (code "70") (name "OUT12_N") (class "Default")
      (node (ref "X-SOUTH") (pin "89") (pinfunction "89_89") (pintype "bidirectional"))
    )
    (net (code "71") (name "OUT12_P") (class "Default")
      (node (ref "X-SOUTH") (pin "87") (pinfunction "87_87") (pintype "bidirectional"))
    )
    (net (code "72") (name "OUT13_N") (class "Default")
      (node (ref "X-SOUTH") (pin "83") (pinfunction "83_83") (pintype "bidirectional"))
      (node (ref "X-WEST") (pin "46") (pinfunction "46_46") (pintype "bidirectional"))
    )
    (net (code "73") (name "OUT13_P") (class "Default")
      (node (ref "X-SOUTH") (pin "81") (pinfunction "81_81") (pintype "bidirectional"))
      (node (ref "X-WEST") (pin "48") (pinfunction "48_48") (pintype "bidirectional"))
    )
    (net (code "74") (name "OUT14_N") (class "Default")
      (node (ref "X-SOUTH") (pin "88") (pinfunction "88_88") (pintype "bidirectional"))
    )
    (net (code "75") (name "OUT14_P") (class "Default")
      (node (ref "X-SOUTH") (pin "86") (pinfunction "86_86") (pintype "bidirectional"))
    )
    (net (code "76") (name "OUT15_N") (class "Default")
      (node (ref "X-EAST") (pin "54") (pinfunction "54_54") (pintype "bidirectional"))
      (node (ref "X-SOUTH") (pin "82") (pinfunction "82_82") (pintype "bidirectional"))
    )
    (net (code "77") (name "OUT15_P") (class "Default")
      (node (ref "X-EAST") (pin "56") (pinfunction "56_56") (pintype "bidirectional"))
      (node (ref "X-SOUTH") (pin "80") (pinfunction "80_80") (pintype "bidirectional"))
    )
    (net (code "78") (name "OUT16_N") (class "Default")
      (node (ref "X-SOUTH") (pin "77") (pinfunction "77_77") (pintype "bidirectional"))
    )
    (net (code "79") (name "OUT16_P") (class "Default")
      (node (ref "X-SOUTH") (pin "75") (pinfunction "75_75") (pintype "bidirectional"))
    )
    (net (code "80") (name "OUT17_N") (class "Default")
      (node (ref "X-EAST") (pin "53") (pinfunction "53_53") (pintype "bidirectional"))
      (node (ref "X-SOUTH") (pin "76") (pinfunction "76_76") (pintype "bidirectional"))
    )
    (net (code "81") (name "OUT17_P") (class "Default")
      (node (ref "X-EAST") (pin "55") (pinfunction "55_55") (pintype "bidirectional"))
      (node (ref "X-SOUTH") (pin "74") (pinfunction "74_74") (pintype "bidirectional"))
    )
    (net (code "82") (name "OUT18_N") (class "Default")
      (node (ref "X-SOUTH") (pin "71") (pinfunction "71_71") (pintype "bidirectional"))
    )
    (net (code "83") (name "OUT18_P") (class "Default")
      (node (ref "X-SOUTH") (pin "69") (pinfunction "69_69") (pintype "bidirectional"))
    )
    (net (code "84") (name "OUT19_N") (class "Default")
      (node (ref "X-EAST") (pin "60") (pinfunction "60_60") (pintype "bidirectional"))
      (node (ref "X-SOUTH") (pin "65") (pinfunction "65_65") (pintype "bidirectional"))
    )
    (net (code "85") (name "OUT19_P") (class "Default")
      (node (ref "X-EAST") (pin "62") (pinfunction "62_62") (pintype "bidirectional"))
      (node (ref "X-SOUTH") (pin "63") (pinfunction "63_63") (pintype "bidirectional"))
    )
    (net (code "86") (name "OUT20_N") (class "Default")
      (node (ref "X-SOUTH") (pin "70") (pinfunction "70_70") (pintype "bidirectional"))
    )
    (net (code "87") (name "OUT20_P") (class "Default")
      (node (ref "X-SOUTH") (pin "68") (pinfunction "68_68") (pintype "bidirectional"))
    )
    (net (code "88") (name "OUT21_N") (class "Default")
      (node (ref "X-EAST") (pin "59") (pinfunction "59_59") (pintype "bidirectional"))
      (node (ref "X-SOUTH") (pin "64") (pinfunction "64_64") (pintype "bidirectional"))
    )
    (net (code "89") (name "OUT21_P") (class "Default")
      (node (ref "X-EAST") (pin "61") (pinfunction "61_61") (pintype "bidirectional"))
      (node (ref "X-SOUTH") (pin "62") (pinfunction "62_62") (pintype "bidirectional"))
    )
    (net (code "90") (name "OUT22_N") (class "Default")
      (node (ref "X-SOUTH") (pin "59") (pinfunction "59_59") (pintype "bidirectional"))
    )
    (net (code "91") (name "OUT22_P") (class "Default")
      (node (ref "X-SOUTH") (pin "57") (pinfunction "57_57") (pintype "bidirectional"))
    )
    (net (code "92") (name "OUT23_N") (class "Default")
      (node (ref "X-EAST") (pin "66") (pinfunction "66_66") (pintype "bidirectional"))
      (node (ref "X-SOUTH") (pin "53") (pinfunction "53_53") (pintype "bidirectional"))
    )
    (net (code "93") (name "OUT23_P") (class "Default")
      (node (ref "X-EAST") (pin "68") (pinfunction "68_68") (pintype "bidirectional"))
      (node (ref "X-SOUTH") (pin "51") (pinfunction "51_51") (pintype "bidirectional"))
    )
    (net (code "94") (name "OUT24_N") (class "Default")
      (node (ref "X-SOUTH") (pin "52") (pinfunction "52_52") (pintype "bidirectional"))
    )
    (net (code "95") (name "OUT24_P") (class "Default")
      (node (ref "X-SOUTH") (pin "50") (pinfunction "50_50") (pintype "bidirectional"))
    )
    (net (code "96") (name "OUT25_N") (class "Default")
      (node (ref "X-EAST") (pin "65") (pinfunction "65_65") (pintype "bidirectional"))
      (node (ref "X-SOUTH") (pin "58") (pinfunction "58_58") (pintype "bidirectional"))
    )
    (net (code "97") (name "OUT25_P") (class "Default")
      (node (ref "X-EAST") (pin "67") (pinfunction "67_67") (pintype "bidirectional"))
      (node (ref "X-SOUTH") (pin "56") (pinfunction "56_56") (pintype "bidirectional"))
    )
    (net (code "98") (name "OUT26_N") (class "Default")
      (node (ref "X-SOUTH") (pin "47") (pinfunction "47_47") (pintype "bidirectional"))
    )
    (net (code "99") (name "OUT26_P") (class "Default")
      (node (ref "X-SOUTH") (pin "45") (pinfunction "45_45") (pintype "bidirectional"))
    )
    (net (code "100") (name "OUT27_N") (class "Default")
      (node (ref "X-EAST") (pin "73") (pinfunction "73_73") (pintype "bidirectional"))
      (node (ref "X-SOUTH") (pin "40") (pinfunction "40_40") (pintype "bidirectional"))
    )
    (net (code "101") (name "OUT27_P") (class "Default")
      (node (ref "X-EAST") (pin "75") (pinfunction "75_75") (pintype "bidirectional"))
      (node (ref "X-SOUTH") (pin "38") (pinfunction "38_38") (pintype "bidirectional"))
    )
    (net (code "102") (name "OUT28_N") (class "Default")
      (node (ref "X-SOUTH") (pin "46") (pinfunction "46_46") (pintype "bidirectional"))
    )
    (net (code "103") (name "OUT28_P") (class "Default")
      (node (ref "X-SOUTH") (pin "44") (pinfunction "44_44") (pintype "bidirectional"))
    )
    (net (code "104") (name "OUT29_N") (class "Default")
      (node (ref "X-EAST") (pin "72") (pinfunction "72_72") (pintype "bidirectional"))
      (node (ref "X-SOUTH") (pin "41") (pinfunction "41_41") (pintype "bidirectional"))
    )
    (net (code "105") (name "OUT29_P") (class "Default")
      (node (ref "X-EAST") (pin "74") (pinfunction "74_74") (pintype "bidirectional"))
      (node (ref "X-SOUTH") (pin "39") (pinfunction "39_39") (pintype "bidirectional"))
    )
    (net (code "106") (name "OUT30_N") (class "Default")
      (node (ref "X-SOUTH") (pin "34") (pinfunction "34_34") (pintype "bidirectional"))
    )
    (net (code "107") (name "OUT30_P") (class "Default")
      (node (ref "X-SOUTH") (pin "32") (pinfunction "32_32") (pintype "bidirectional"))
    )
    (net (code "108") (name "OUT31_N") (class "Default")
      (node (ref "X-EAST") (pin "78") (pinfunction "78_78") (pintype "bidirectional"))
      (node (ref "X-SOUTH") (pin "35") (pinfunction "35_35") (pintype "bidirectional"))
    )
    (net (code "109") (name "OUT31_P") (class "Default")
      (node (ref "X-EAST") (pin "80") (pinfunction "80_80") (pintype "bidirectional"))
      (node (ref "X-SOUTH") (pin "33") (pinfunction "33_33") (pintype "bidirectional"))
    )
    (net (code "110") (name "OUT32_N") (class "Default")
      (node (ref "X-SOUTH") (pin "28") (pinfunction "28_28") (pintype "bidirectional"))
    )
    (net (code "111") (name "OUT32_P") (class "Default")
      (node (ref "X-SOUTH") (pin "26") (pinfunction "26_26") (pintype "bidirectional"))
    )
    (net (code "112") (name "OUT33_N") (class "Default")
      (node (ref "X-NORTH") (pin "20") (pinfunction "20_20") (pintype "bidirectional"))
      (node (ref "X-WEST") (pin "67") (pinfunction "67_67") (pintype "bidirectional"))
    )
    (net (code "113") (name "OUT33_P") (class "Default")
      (node (ref "X-NORTH") (pin "22") (pinfunction "22_22") (pintype "bidirectional"))
      (node (ref "X-WEST") (pin "65") (pinfunction "65_65") (pintype "bidirectional"))
    )
    (net (code "114") (name "OUT34_N") (class "Default")
      (node (ref "X-NORTH") (pin "27") (pinfunction "27_27") (pintype "bidirectional"))
    )
    (net (code "115") (name "OUT34_P") (class "Default")
      (node (ref "X-NORTH") (pin "29") (pinfunction "29_29") (pintype "bidirectional"))
    )
    (net (code "116") (name "OUT35_N") (class "Default")
      (node (ref "X-NORTH") (pin "26") (pinfunction "26_26") (pintype "bidirectional"))
      (node (ref "X-WEST") (pin "61") (pinfunction "61_61") (pintype "bidirectional"))
    )
    (net (code "117") (name "OUT35_P") (class "Default")
      (node (ref "X-NORTH") (pin "28") (pinfunction "28_28") (pintype "bidirectional"))
      (node (ref "X-WEST") (pin "59") (pinfunction "59_59") (pintype "bidirectional"))
    )
    (net (code "118") (name "OUT36_N") (class "Default")
      (node (ref "X-NORTH") (pin "33") (pinfunction "33_33") (pintype "bidirectional"))
    )
    (net (code "119") (name "OUT36_P") (class "Default")
      (node (ref "X-NORTH") (pin "35") (pinfunction "35_35") (pintype "bidirectional"))
    )
    (net (code "120") (name "OUT37_N") (class "Default")
      (node (ref "X-NORTH") (pin "32") (pinfunction "32_32") (pintype "bidirectional"))
      (node (ref "X-WEST") (pin "47") (pinfunction "47_47") (pintype "bidirectional"))
    )
    (net (code "121") (name "OUT37_P") (class "Default")
      (node (ref "X-NORTH") (pin "34") (pinfunction "34_34") (pintype "bidirectional"))
      (node (ref "X-WEST") (pin "45") (pinfunction "45_45") (pintype "bidirectional"))
    )
    (net (code "122") (name "OUT38_N") (class "Default")
      (node (ref "X-NORTH") (pin "38") (pinfunction "38_38") (pintype "bidirectional"))
    )
    (net (code "123") (name "OUT38_P") (class "Default")
      (node (ref "X-NORTH") (pin "40") (pinfunction "40_40") (pintype "bidirectional"))
    )
    (net (code "124") (name "OUT39_N") (class "Default")
      (node (ref "X-NORTH") (pin "39") (pinfunction "39_39") (pintype "bidirectional"))
      (node (ref "X-WEST") (pin "80") (pinfunction "80_80") (pintype "bidirectional"))
    )
    (net (code "125") (name "OUT39_P") (class "Default")
      (node (ref "X-NORTH") (pin "41") (pinfunction "41_41") (pintype "bidirectional"))
      (node (ref "X-WEST") (pin "78") (pinfunction "78_78") (pintype "bidirectional"))
    )
    (net (code "126") (name "OUT40_N") (class "Default")
      (node (ref "X-NORTH") (pin "44") (pinfunction "44_44") (pintype "bidirectional"))
    )
    (net (code "127") (name "OUT40_P") (class "Default")
      (node (ref "X-NORTH") (pin "46") (pinfunction "46_46") (pintype "bidirectional"))
    )
    (net (code "128") (name "OUT41_N") (class "Default")
      (node (ref "X-NORTH") (pin "45") (pinfunction "45_45") (pintype "bidirectional"))
      (node (ref "X-WEST") (pin "74") (pinfunction "74_74") (pintype "bidirectional"))
    )
    (net (code "129") (name "OUT41_P") (class "Default")
      (node (ref "X-NORTH") (pin "47") (pinfunction "47_47") (pintype "bidirectional"))
      (node (ref "X-WEST") (pin "72") (pinfunction "72_72") (pintype "bidirectional"))
    )
    (net (code "130") (name "OUT42_N") (class "Default")
      (node (ref "X-NORTH") (pin "50") (pinfunction "50_50") (pintype "bidirectional"))
    )
    (net (code "131") (name "OUT42_P") (class "Default")
      (node (ref "X-NORTH") (pin "52") (pinfunction "52_52") (pintype "bidirectional"))
    )
    (net (code "132") (name "OUT43_N") (class "Default")
      (node (ref "X-NORTH") (pin "51") (pinfunction "51_51") (pintype "bidirectional"))
      (node (ref "X-WEST") (pin "68") (pinfunction "68_68") (pintype "bidirectional"))
    )
    (net (code "133") (name "OUT43_P") (class "Default")
      (node (ref "X-NORTH") (pin "53") (pinfunction "53_53") (pintype "bidirectional"))
      (node (ref "X-WEST") (pin "66") (pinfunction "66_66") (pintype "bidirectional"))
    )
    (net (code "134") (name "OUT44_N") (class "Default")
      (node (ref "X-NORTH") (pin "56") (pinfunction "56_56") (pintype "bidirectional"))
    )
    (net (code "135") (name "OUT44_P") (class "Default")
      (node (ref "X-NORTH") (pin "58") (pinfunction "58_58") (pintype "bidirectional"))
    )
    (net (code "136") (name "OUT45_N") (class "Default")
      (node (ref "X-NORTH") (pin "57") (pinfunction "57_57") (pintype "bidirectional"))
      (node (ref "X-WEST") (pin "62") (pinfunction "62_62") (pintype "bidirectional"))
    )
    (net (code "137") (name "OUT45_P") (class "Default")
      (node (ref "X-NORTH") (pin "59") (pinfunction "59_59") (pintype "bidirectional"))
      (node (ref "X-WEST") (pin "60") (pinfunction "60_60") (pintype "bidirectional"))
    )
    (net (code "138") (name "OUT46_N") (class "Default")
      (node (ref "X-NORTH") (pin "62") (pinfunction "62_62") (pintype "bidirectional"))
    )
    (net (code "139") (name "OUT46_P") (class "Default")
      (node (ref "X-NORTH") (pin "64") (pinfunction "64_64") (pintype "bidirectional"))
    )
    (net (code "140") (name "OUT47_N") (class "Default")
      (node (ref "X-NORTH") (pin "63") (pinfunction "63_63") (pintype "bidirectional"))
      (node (ref "X-WEST") (pin "56") (pinfunction "56_56") (pintype "bidirectional"))
    )
    (net (code "141") (name "OUT47_P") (class "Default")
      (node (ref "X-NORTH") (pin "65") (pinfunction "65_65") (pintype "bidirectional"))
      (node (ref "X-WEST") (pin "54") (pinfunction "54_54") (pintype "bidirectional"))
    )
    (net (code "142") (name "OUT48_N") (class "Default")
      (node (ref "X-NORTH") (pin "68") (pinfunction "68_68") (pintype "bidirectional"))
    )
    (net (code "143") (name "OUT48_P") (class "Default")
      (node (ref "X-NORTH") (pin "70") (pinfunction "70_70") (pintype "bidirectional"))
    )
    (net (code "144") (name "OUT49_N") (class "Default")
      (node (ref "X-EAST") (pin "48") (pinfunction "48_48") (pintype "bidirectional"))
      (node (ref "X-NORTH") (pin "74") (pinfunction "74_74") (pintype "bidirectional"))
    )
    (net (code "145") (name "OUT49_P") (class "Default")
      (node (ref "X-EAST") (pin "46") (pinfunction "46_46") (pintype "bidirectional"))
      (node (ref "X-NORTH") (pin "76") (pinfunction "76_76") (pintype "bidirectional"))
    )
    (net (code "146") (name "OUT50_N") (class "Default")
      (node (ref "X-NORTH") (pin "69") (pinfunction "69_69") (pintype "bidirectional"))
    )
    (net (code "147") (name "OUT50_P") (class "Default")
      (node (ref "X-NORTH") (pin "71") (pinfunction "71_71") (pintype "bidirectional"))
    )
    (net (code "148") (name "OUT51_N") (class "Default")
      (node (ref "X-EAST") (pin "42") (pinfunction "42_42") (pintype "bidirectional"))
      (node (ref "X-NORTH") (pin "80") (pinfunction "80_80") (pintype "bidirectional"))
    )
    (net (code "149") (name "OUT51_P") (class "Default")
      (node (ref "X-EAST") (pin "40") (pinfunction "40_40") (pintype "bidirectional"))
      (node (ref "X-NORTH") (pin "82") (pinfunction "82_82") (pintype "bidirectional"))
    )
    (net (code "150") (name "OUT52_N") (class "Default")
      (node (ref "X-NORTH") (pin "75") (pinfunction "75_75") (pintype "bidirectional"))
    )
    (net (code "151") (name "OUT52_P") (class "Default")
      (node (ref "X-NORTH") (pin "77") (pinfunction "77_77") (pintype "bidirectional"))
    )
    (net (code "152") (name "OUT53_N") (class "Default")
      (node (ref "X-EAST") (pin "47") (pinfunction "47_47") (pintype "bidirectional"))
      (node (ref "X-NORTH") (pin "86") (pinfunction "86_86") (pintype "bidirectional"))
    )
    (net (code "153") (name "OUT53_P") (class "Default")
      (node (ref "X-EAST") (pin "45") (pinfunction "45_45") (pintype "bidirectional"))
      (node (ref "X-NORTH") (pin "88") (pinfunction "88_88") (pintype "bidirectional"))
    )
    (net (code "154") (name "OUT54_N") (class "Default")
      (node (ref "X-NORTH") (pin "81") (pinfunction "81_81") (pintype "bidirectional"))
    )
    (net (code "155") (name "OUT54_P") (class "Default")
      (node (ref "X-NORTH") (pin "83") (pinfunction "83_83") (pintype "bidirectional"))
    )
    (net (code "156") (name "OUT55_N") (class "Default")
      (node (ref "X-EAST") (pin "41") (pinfunction "41_41") (pintype "bidirectional"))
      (node (ref "X-NORTH") (pin "92") (pinfunction "92_92") (pintype "bidirectional"))
    )
    (net (code "157") (name "OUT55_P") (class "Default")
      (node (ref "X-EAST") (pin "39") (pinfunction "39_39") (pintype "bidirectional"))
      (node (ref "X-NORTH") (pin "94") (pinfunction "94_94") (pintype "bidirectional"))
    )
    (net (code "158") (name "OUT56_N") (class "Default")
      (node (ref "X-NORTH") (pin "87") (pinfunction "87_87") (pintype "bidirectional"))
    )
    (net (code "159") (name "OUT56_P") (class "Default")
      (node (ref "X-NORTH") (pin "89") (pinfunction "89_89") (pintype "bidirectional"))
    )
    (net (code "160") (name "OUT57_N") (class "Default")
      (node (ref "X-EAST") (pin "35") (pinfunction "35_35") (pintype "bidirectional"))
      (node (ref "X-NORTH") (pin "98") (pinfunction "98_98") (pintype "bidirectional"))
    )
    (net (code "161") (name "OUT57_P") (class "Default")
      (node (ref "X-EAST") (pin "33") (pinfunction "33_33") (pintype "bidirectional"))
      (node (ref "X-NORTH") (pin "100") (pinfunction "100_100") (pintype "bidirectional"))
    )
    (net (code "162") (name "OUT58_N") (class "Default")
      (node (ref "X-NORTH") (pin "93") (pinfunction "93_93") (pintype "bidirectional"))
    )
    (net (code "163") (name "OUT58_P") (class "Default")
      (node (ref "X-NORTH") (pin "95") (pinfunction "95_95") (pintype "bidirectional"))
    )
    (net (code "164") (name "OUT59_N") (class "Default")
      (node (ref "X-EAST") (pin "27") (pinfunction "27_27") (pintype "bidirectional"))
      (node (ref "X-NORTH") (pin "104") (pinfunction "104_104") (pintype "bidirectional"))
    )
    (net (code "165") (name "OUT59_P") (class "Default")
      (node (ref "X-EAST") (pin "25") (pinfunction "25_25") (pintype "bidirectional"))
      (node (ref "X-NORTH") (pin "106") (pinfunction "106_106") (pintype "bidirectional"))
    )
    (net (code "166") (name "OUT60_N") (class "Default")
      (node (ref "X-NORTH") (pin "110") (pinfunction "110_110") (pintype "bidirectional"))
    )
    (net (code "167") (name "OUT60_P") (class "Default")
      (node (ref "X-NORTH") (pin "112") (pinfunction "112_112") (pintype "bidirectional"))
    )
    (net (code "168") (name "OUT61_N") (class "Default")
      (node (ref "X-EAST") (pin "36") (pinfunction "36_36") (pintype "bidirectional"))
      (node (ref "X-NORTH") (pin "99") (pinfunction "99_99") (pintype "bidirectional"))
    )
    (net (code "169") (name "OUT61_P") (class "Default")
      (node (ref "X-EAST") (pin "34") (pinfunction "34_34") (pintype "bidirectional"))
      (node (ref "X-NORTH") (pin "101") (pinfunction "101_101") (pintype "bidirectional"))
    )
    (net (code "170") (name "OUT62_N") (class "Default")
      (node (ref "X-NORTH") (pin "116") (pinfunction "116_116") (pintype "bidirectional"))
    )
    (net (code "171") (name "OUT62_P") (class "Default")
      (node (ref "X-NORTH") (pin "118") (pinfunction "118_118") (pintype "bidirectional"))
    )
    (net (code "172") (name "OUT63_N") (class "Default")
      (node (ref "X-EAST") (pin "30") (pinfunction "30_30") (pintype "bidirectional"))
      (node (ref "X-NORTH") (pin "105") (pinfunction "105_105") (pintype "bidirectional"))
    )
    (net (code "173") (name "OUT63_P") (class "Default")
      (node (ref "X-EAST") (pin "28") (pinfunction "28_28") (pintype "bidirectional"))
      (node (ref "X-NORTH") (pin "107") (pinfunction "107_107") (pintype "bidirectional"))
    )
    (net (code "174") (name "OUT64_N") (class "Default")
      (node (ref "X-NORTH") (pin "111") (pinfunction "111_111") (pintype "bidirectional"))
    )
    (net (code "175") (name "OUT64_P") (class "Default")
      (node (ref "X-NORTH") (pin "113") (pinfunction "113_113") (pintype "bidirectional"))
    )
    (net (code "176") (name "OUTCLK_N") (class "Default")
      (node (ref "X-NORTH") (pin "15") (pinfunction "15_15") (pintype "bidirectional"))
      (node (ref "X-WEST") (pin "53") (pinfunction "53_53") (pintype "bidirectional"))
    )
    (net (code "177") (name "OUTCLK_P") (class "Default")
      (node (ref "X-NORTH") (pin "17") (pinfunction "17_17") (pintype "bidirectional"))
      (node (ref "X-WEST") (pin "55") (pinfunction "55_55") (pintype "bidirectional"))
    )
    (net (code "178") (name "OUTCTR_N") (class "Default")
      (node (ref "X-SOUTH") (pin "125") (pinfunction "125_125") (pintype "bidirectional"))
      (node (ref "X-WEST") (pin "22") (pinfunction "22_22") (pintype "bidirectional"))
    )
    (net (code "179") (name "OUTCTR_P") (class "Default")
      (node (ref "X-SOUTH") (pin "123") (pinfunction "123_123") (pintype "bidirectional"))
      (node (ref "X-WEST") (pin "24") (pinfunction "24_24") (pintype "bidirectional"))
    )
    (net (code "180") (name "RES1") (class "Default")
      (node (ref "X-WEST") (pin "79") (pinfunction "79_79") (pintype "bidirectional"))
    )
    (net (code "181") (name "RES2") (class "Default")
      (node (ref "X-WEST") (pin "81") (pinfunction "81_81") (pintype "bidirectional"))
    )
    (net (code "182") (name "RES3") (class "Default")
      (node (ref "X-WEST") (pin "83") (pinfunction "83_83") (pintype "bidirectional"))
    )
    (net (code "183") (name "RES4") (class "Default")
      (node (ref "X-EAST") (pin "79") (pinfunction "79_79") (pintype "bidirectional"))
    )
    (net (code "184") (name "RES5") (class "Default")
      (node (ref "X-EAST") (pin "81") (pinfunction "81_81") (pintype "bidirectional"))
    )
    (net (code "185") (name "RES6") (class "Default")
      (node (ref "X-EAST") (pin "83") (pinfunction "83_83") (pintype "bidirectional"))
    )
    (net (code "186") (name "S00_N") (class "Default")
      (node (ref "X-SOUTH") (pin "16") (pinfunction "16_16") (pintype "bidirectional"))
    )
    (net (code "187") (name "S00_P") (class "Default")
      (node (ref "X-SOUTH") (pin "14") (pinfunction "14_14") (pintype "bidirectional"))
    )
    (net (code "188") (name "S01_N") (class "Default")
      (node (ref "X-SOUTH") (pin "17") (pinfunction "17_17") (pintype "bidirectional"))
    )
    (net (code "189") (name "S01_P") (class "Default")
      (node (ref "X-SOUTH") (pin "15") (pinfunction "15_15") (pintype "bidirectional"))
    )
    (net (code "190") (name "S02_N") (class "Default")
      (node (ref "X-SOUTH") (pin "22") (pinfunction "22_22") (pintype "bidirectional"))
    )
    (net (code "191") (name "S02_P") (class "Default")
      (node (ref "X-SOUTH") (pin "20") (pinfunction "20_20") (pintype "bidirectional"))
    )
    (net (code "192") (name "S03_N") (class "Default")
      (node (ref "X-SOUTH") (pin "23") (pinfunction "23_23") (pintype "bidirectional"))
    )
    (net (code "193") (name "S03_P") (class "Default")
      (node (ref "X-SOUTH") (pin "21") (pinfunction "21_21") (pintype "bidirectional"))
    )
    (net (code "194") (name "S05_N") (class "Default")
      (node (ref "X-SOUTH") (pin "29") (pinfunction "29_29") (pintype "bidirectional"))
    )
    (net (code "195") (name "S05_P") (class "Default")
      (node (ref "X-SOUTH") (pin "27") (pinfunction "27_27") (pintype "bidirectional"))
    )
    (net (code "196") (name "S38_N") (class "Default")
      (node (ref "X-SOUTH") (pin "130") (pinfunction "130_130") (pintype "bidirectional"))
    )
    (net (code "197") (name "S38_P") (class "Default")
      (node (ref "X-SOUTH") (pin "128") (pinfunction "128_128") (pintype "bidirectional"))
    )
    (net (code "198") (name "S39_N") (class "Default")
      (node (ref "X-SOUTH") (pin "131") (pinfunction "131_131") (pintype "bidirectional"))
    )
    (net (code "199") (name "S39_P") (class "Default")
      (node (ref "X-SOUTH") (pin "129") (pinfunction "129_129") (pintype "bidirectional"))
    )
    (net (code "200") (name "SYS_RES_N") (class "Default")
      (node (ref "X-EAST") (pin "22") (pinfunction "22_22") (pintype "bidirectional"))
      (node (ref "X-NORTH") (pin "125") (pinfunction "125_125") (pintype "bidirectional"))
    )
    (net (code "201") (name "S_CHK_EN") (class "Default")
      (node (ref "X-EAST") (pin "94") (pinfunction "94_94") (pintype "bidirectional"))
      (node (ref "X-SOUTH") (pin "8") (pinfunction "8_8") (pintype "bidirectional"))
    )
    (net (code "202") (name "S_CHK_V") (class "Default")
      (node (ref "X-EAST") (pin "92") (pinfunction "92_92") (pintype "bidirectional"))
      (node (ref "X-SOUTH") (pin "10") (pinfunction "10_10") (pintype "bidirectional"))
    )
    (net (code "203") (name "S_I2C_EN") (class "Default")
      (node (ref "X-SOUTH") (pin "137") (pinfunction "137_137") (pintype "bidirectional"))
      (node (ref "X-WEST") (pin "7") (pinfunction "7_7") (pintype "bidirectional"))
    )
    (net (code "204") (name "S_I2C_V") (class "Default")
      (node (ref "X-SOUTH") (pin "135") (pinfunction "135_135") (pintype "bidirectional"))
      (node (ref "X-WEST") (pin "9") (pinfunction "9_9") (pintype "bidirectional"))
    )
    (net (code "205") (name "S_SCK") (class "Default")
      (node (ref "X-SOUTH") (pin "144") (pinfunction "144_144") (pintype "bidirectional"))
      (node (ref "X-WEST") (pin "2") (pinfunction "2_2") (pintype "bidirectional"))
    )
    (net (code "206") (name "S_SCL") (class "Default")
      (node (ref "X-SOUTH") (pin "143") (pinfunction "143_143") (pintype "bidirectional"))
      (node (ref "X-WEST") (pin "1") (pinfunction "1_1") (pintype "bidirectional"))
    )
    (net (code "207") (name "S_SDA") (class "Default")
      (node (ref "X-SOUTH") (pin "141") (pinfunction "141_141") (pintype "bidirectional"))
      (node (ref "X-WEST") (pin "3") (pinfunction "3_3") (pintype "bidirectional"))
    )
    (net (code "208") (name "S_SDI") (class "Default")
      (node (ref "X-SOUTH") (pin "140") (pinfunction "140_140") (pintype "bidirectional"))
      (node (ref "X-WEST") (pin "6") (pinfunction "6_6") (pintype "bidirectional"))
    )
    (net (code "209") (name "S_SDO") (class "Default")
      (node (ref "X-SOUTH") (pin "142") (pinfunction "142_142") (pintype "bidirectional"))
      (node (ref "X-WEST") (pin "4") (pinfunction "4_4") (pintype "bidirectional"))
    )
    (net (code "210") (name "S_SPI_EN") (class "Default")
      (node (ref "X-SOUTH") (pin "136") (pinfunction "136_136") (pintype "bidirectional"))
      (node (ref "X-WEST") (pin "8") (pinfunction "8_8") (pintype "bidirectional"))
    )
    (net (code "211") (name "S_SPI_V") (class "Default")
      (node (ref "X-SOUTH") (pin "134") (pinfunction "134_134") (pintype "bidirectional"))
      (node (ref "X-WEST") (pin "10") (pinfunction "10_10") (pintype "bidirectional"))
    )
    (net (code "212") (name "S_VE") (class "Default")
      (node (ref "C7") (pin "1") (pinfunction "1_1") (pintype "passive"))
      (node (ref "SE") (pin "1") (pinfunction "1_1") (pintype "passive"))
      (node (ref "X-SOUTH") (pin "13") (pinfunction "13_13") (pintype "bidirectional"))
      (node (ref "X-SOUTH") (pin "19") (pinfunction "19_19") (pintype "bidirectional"))
      (node (ref "X-SOUTH") (pin "31") (pinfunction "31_31") (pintype "bidirectional"))
      (node (ref "X-SOUTH") (pin "37") (pinfunction "37_37") (pintype "bidirectional"))
    )
    (net (code "213") (name "S_VE_CV") (class "Default")
      (node (ref "X-EAST") (pin "100") (pinfunction "100_100") (pintype "bidirectional"))
      (node (ref "X-SOUTH") (pin "2") (pinfunction "2_2") (pintype "bidirectional"))
    )
    (net (code "214") (name "S_VE_OV") (class "Default")
      (node (ref "X-EAST") (pin "99") (pinfunction "99_99") (pintype "bidirectional"))
      (node (ref "X-SOUTH") (pin "1") (pinfunction "1_1") (pintype "bidirectional"))
    )
    (net (code "215") (name "S_VE_RS") (class "Default")
      (node (ref "X-EAST") (pin "84") (pinfunction "84_84") (pintype "bidirectional"))
      (node (ref "X-SOUTH") (pin "25") (pinfunction "25_25") (pintype "bidirectional"))
    )
    (net (code "216") (name "S_VE_UV") (class "Default")
      (node (ref "X-EAST") (pin "89") (pinfunction "89_89") (pintype "bidirectional"))
      (node (ref "X-SOUTH") (pin "7") (pinfunction "7_7") (pintype "bidirectional"))
    )
    (net (code "217") (name "S_VS") (class "Default")
      (node (ref "C6") (pin "1") (pinfunction "1_1") (pintype "passive"))
      (node (ref "SW") (pin "1") (pinfunction "1_1") (pintype "passive"))
      (node (ref "X-SOUTH") (pin "49") (pinfunction "49_49") (pintype "bidirectional"))
      (node (ref "X-SOUTH") (pin "55") (pinfunction "55_55") (pintype "bidirectional"))
      (node (ref "X-SOUTH") (pin "61") (pinfunction "61_61") (pintype "bidirectional"))
      (node (ref "X-SOUTH") (pin "67") (pinfunction "67_67") (pintype "bidirectional"))
      (node (ref "X-SOUTH") (pin "79") (pinfunction "79_79") (pintype "bidirectional"))
      (node (ref "X-SOUTH") (pin "85") (pinfunction "85_85") (pintype "bidirectional"))
      (node (ref "X-SOUTH") (pin "91") (pinfunction "91_91") (pintype "bidirectional"))
      (node (ref "X-SOUTH") (pin "97") (pinfunction "97_97") (pintype "bidirectional"))
    )
    (net (code "218") (name "S_VS_CV") (class "Default")
      (node (ref "X-EAST") (pin "98") (pinfunction "98_98") (pintype "bidirectional"))
      (node (ref "X-SOUTH") (pin "4") (pinfunction "4_4") (pintype "bidirectional"))
    )
    (net (code "219") (name "S_VS_OV") (class "Default")
      (node (ref "X-EAST") (pin "97") (pinfunction "97_97") (pintype "bidirectional"))
      (node (ref "X-SOUTH") (pin "3") (pinfunction "3_3") (pintype "bidirectional"))
    )
    (net (code "220") (name "S_VS_RS") (class "Default")
      (node (ref "X-EAST") (pin "86") (pinfunction "86_86") (pintype "bidirectional"))
      (node (ref "X-SOUTH") (pin "73") (pinfunction "73_73") (pintype "bidirectional"))
    )
    (net (code "221") (name "S_VS_UV") (class "Default")
      (node (ref "X-EAST") (pin "87") (pinfunction "87_87") (pintype "bidirectional"))
      (node (ref "X-SOUTH") (pin "9") (pinfunction "9_9") (pintype "bidirectional"))
    )
    (net (code "222") (name "S_VW") (class "Default")
      (node (ref "C2") (pin "1") (pinfunction "1_1") (pintype "passive"))
      (node (ref "SW") (pin "2") (pinfunction "2_2") (pintype "passive"))
      (node (ref "X-SOUTH") (pin "109") (pinfunction "109_109") (pintype "bidirectional"))
      (node (ref "X-SOUTH") (pin "115") (pinfunction "115_115") (pintype "bidirectional"))
      (node (ref "X-SOUTH") (pin "127") (pinfunction "127_127") (pintype "bidirectional"))
      (node (ref "X-SOUTH") (pin "133") (pinfunction "133_133") (pintype "bidirectional"))
    )
    (net (code "223") (name "S_VW_CV") (class "Default")
      (node (ref "X-EAST") (pin "96") (pinfunction "96_96") (pintype "bidirectional"))
      (node (ref "X-SOUTH") (pin "6") (pinfunction "6_6") (pintype "bidirectional"))
    )
    (net (code "224") (name "S_VW_OV") (class "Default")
      (node (ref "X-EAST") (pin "95") (pinfunction "95_95") (pintype "bidirectional"))
      (node (ref "X-SOUTH") (pin "5") (pinfunction "5_5") (pintype "bidirectional"))
    )
    (net (code "225") (name "S_VW_RS") (class "Default")
      (node (ref "X-EAST") (pin "88") (pinfunction "88_88") (pintype "bidirectional"))
      (node (ref "X-SOUTH") (pin "121") (pinfunction "121_121") (pintype "bidirectional"))
    )
    (net (code "226") (name "S_VW_UV") (class "Default")
      (node (ref "X-EAST") (pin "85") (pinfunction "85_85") (pintype "bidirectional"))
      (node (ref "X-SOUTH") (pin "11") (pinfunction "11_11") (pintype "bidirectional"))
    )
    (net (code "227") (name "TCK") (class "Default")
      (node (ref "X-WEST") (pin "12") (pinfunction "12_12") (pintype "bidirectional"))
    )
    (net (code "228") (name "TDI") (class "Default")
      (node (ref "X-WEST") (pin "16") (pinfunction "16_16") (pintype "bidirectional"))
    )
    (net (code "229") (name "TDIG1") (class "Default")
      (node (ref "X-EAST") (pin "18") (pinfunction "18_18") (pintype "bidirectional"))
      (node (ref "X-NORTH") (pin "123") (pinfunction "123_123") (pintype "bidirectional"))
    )
    (net (code "230") (name "TDIG2") (class "Default")
      (node (ref "X-NORTH") (pin "130") (pinfunction "130_130") (pintype "bidirectional"))
    )
    (net (code "231") (name "TDO") (class "Default")
      (node (ref "X-WEST") (pin "18") (pinfunction "18_18") (pintype "bidirectional"))
    )
    (net (code "232") (name "TMS") (class "Default")
      (node (ref "X-WEST") (pin "14") (pinfunction "14_14") (pintype "bidirectional"))
    )
    (net (code "233") (name "TP9") (class "Default")
      (node (ref "X-NORTH") (pin "119") (pinfunction "119_119") (pintype "bidirectional"))
    )
    (net (code "234") (name "T_EXP1") (class "Default")
      (node (ref "X-EAST") (pin "12") (pinfunction "12_12") (pintype "bidirectional"))
      (node (ref "X-NORTH") (pin "131") (pinfunction "131_131") (pintype "bidirectional"))
    )
    (net (code "235") (name "T_EXP2") (class "Default")
      (node (ref "X-EAST") (pin "16") (pinfunction "16_16") (pintype "bidirectional"))
      (node (ref "X-NORTH") (pin "117") (pinfunction "117_117") (pintype "bidirectional"))
    )
    (net (code "236") (name "W_EN") (class "Default")
      (node (ref "X-WEST") (pin "19") (pinfunction "19_19") (pintype "bidirectional"))
    )
    (net (code "237") (name "W_I2C_EN") (class "Default")
      (node (ref "X-WEST") (pin "13") (pinfunction "13_13") (pintype "bidirectional"))
    )
    (net (code "238") (name "W_I2C_V") (class "Default")
      (node (ref "X-WEST") (pin "11") (pinfunction "11_11") (pintype "bidirectional"))
    )
    (net (code "239") (name "W_SCL") (class "Default")
      (node (ref "X-WEST") (pin "15") (pinfunction "15_15") (pintype "bidirectional"))
    )
    (net (code "240") (name "W_SDA") (class "Default")
      (node (ref "X-WEST") (pin "17") (pinfunction "17_17") (pintype "bidirectional"))
    )
    (net (code "241") (name "W_VW") (class "Default")
      (node (ref "C8") (pin "1") (pinfunction "1_1") (pintype "passive"))
      (node (ref "NW") (pin "2") (pinfunction "2_2") (pintype "passive"))
    )
    (net (code "242") (name "W_VW_CV") (class "Default")
      (node (ref "X-WEST") (pin "90") (pinfunction "90_90") (pintype "bidirectional"))
    )
    (net (code "243") (name "W_VW_OV") (class "Default")
      (node (ref "X-WEST") (pin "93") (pinfunction "93_93") (pintype "bidirectional"))
    )
    (net (code "244") (name "W_VW_UV") (class "Default")
      (node (ref "X-WEST") (pin "91") (pinfunction "91_91") (pintype "bidirectional"))
    )
    (net (code "245") (name "unconnected-(X-EAST-PadM1)") (class "Default")
      (node (ref "X-EAST") (pin "M1") (pinfunction "M1_M1") (pintype "bidirectional"))
    )
    (net (code "246") (name "unconnected-(X-EAST-PadM2)") (class "Default")
      (node (ref "X-EAST") (pin "M2") (pinfunction "M2_M2") (pintype "bidirectional"))
    )
    (net (code "247") (name "unconnected-(X-NORTH-PadM1)") (class "Default")
      (node (ref "X-NORTH") (pin "M1") (pinfunction "M1_M1") (pintype "bidirectional"))
    )
    (net (code "248") (name "unconnected-(X-NORTH-PadM2)") (class "Default")
      (node (ref "X-NORTH") (pin "M2") (pinfunction "M2_M2") (pintype "bidirectional"))
    )
    (net (code "249") (name "unconnected-(X-SOUTH-PadM1)") (class "Default")
      (node (ref "X-SOUTH") (pin "M1") (pinfunction "M1_M1") (pintype "bidirectional"))
    )
    (net (code "250") (name "unconnected-(X-SOUTH-PadM2)") (class "Default")
      (node (ref "X-SOUTH") (pin "M2") (pinfunction "M2_M2") (pintype "bidirectional"))
    )
    (net (code "251") (name "unconnected-(X-WEST-PadM1)") (class "Default")
      (node (ref "X-WEST") (pin "M1") (pinfunction "M1_M1") (pintype "bidirectional"))
    )
    (net (code "252") (name "unconnected-(X-WEST-PadM2)") (class "Default")
      (node (ref "X-WEST") (pin "M2") (pinfunction "M2_M2") (pintype "bidirectional"))
    )
  )
)
